# Rele-12V-FritzenLab-Testes.net
KiCad netlist of a schematic drawn in EAGLE
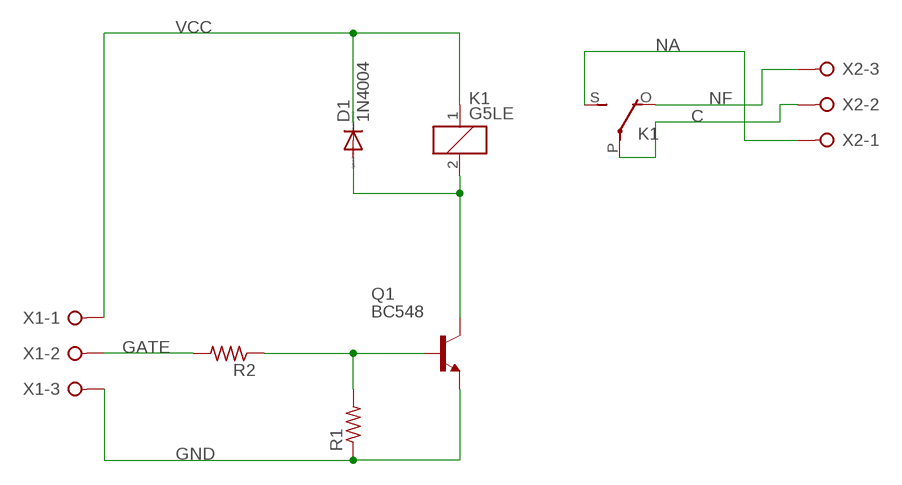
[diagram p0: schematic, sheet 1]

(export (version "E")
  (design (tool "Eeschema 10.0.6"))
  (components
    (comp (ref "D1")
      (value "1N4004")
      (footprint "eagle-import:DO41-10")
      (libsource (lib "eagle-import") (part "1N4004"))
    )
    (comp (ref "K1")
      (value "G5LE")
      (footprint "eagle-import:G5LE")
      (libsource (lib "eagle-import") (part "G5LE"))
    )
    (comp (ref "Q1")
      (value "BC548")
      (footprint "eagle-import:TO92-EBC")
      (libsource (lib "eagle-import") (part "BC548"))
    )
    (comp (ref "R1")
      (value "R-US_0207/10")
      (footprint "eagle-import:0207_10")
      (libsource (lib "eagle-import") (part "R-US_0207/10"))
    )
    (comp (ref "R2")
      (value "R-US_0207/10")
      (footprint "eagle-import:0207_10")
      (libsource (lib "eagle-import") (part "R-US_0207/10"))
    )
    (comp (ref "X1")
      (value "W237-3E")
      (footprint "eagle-import:W237-3E")
      (libsource (lib "eagle-import") (part "W237-3E"))
    )
    (comp (ref "X2")
      (value "W237-3E")
      (footprint "eagle-import:W237-3E")
      (libsource (lib "eagle-import") (part "W237-3E"))
    )
  )
  (nets
    (net (code "1") (name "/C") (class "Default")
      (node (ref "K1") (pin "P") (pinfunction "P_P") (pintype "passive"))
      (node (ref "X2") (pin "2") (pinfunction "KL_2") (pintype "passive"))
    )
    (net (code "2") (name "/GATE") (class "Default")
      (node (ref "R2") (pin "2") (pinfunction "2_2") (pintype "passive"))
      (node (ref "X1") (pin "2") (pinfunction "KL_2") (pintype "passive"))
    )
    (net (code "3") (name "/GND") (class "Default")
      (node (ref "Q1") (pin "E") (pinfunction "E_E") (pintype "passive"))
      (node (ref "R1") (pin "1") (pinfunction "1_1") (pintype "passive"))
      (node (ref "X1") (pin "3") (pinfunction "KL_3") (pintype "passive"))
    )
    (net (code "4") (name "/NA") (class "Default")
      (node (ref "K1") (pin "S") (pinfunction "S_S") (pintype "passive"))
      (node (ref "X2") (pin "1") (pinfunction "KL_1") (pintype "passive"))
    )
    (net (code "5") (name "/NF") (class "Default")
      (node (ref "K1") (pin "O") (pinfunction "O_O") (pintype "passive"))
      (node (ref "X2") (pin "3") (pinfunction "KL_3") (pintype "passive"))
    )
    (net (code "6") (name "/VCC") (class "Default")
      (node (ref "D1") (pin "C") (pinfunction "C_C") (pintype "passive"))
      (node (ref "K1") (pin "1") (pinfunction "1_1") (pintype "passive"))
      (node (ref "X1") (pin "1") (pinfunction "KL_1") (pintype "passive"))
    )
    (net (code "7") (name "Net-(D1-PadA)") (class "Default")
      (node (ref "D1") (pin "A") (pinfunction "A_A") (pintype "passive"))
      (node (ref "K1") (pin "2") (pinfunction "2_2") (pintype "passive"))
      (node (ref "Q1") (pin "C") (pinfunction "C_C") (pintype "passive"))
    )
    (net (code "8") (name "Net-(Q1-PadB)") (class "Default")
      (node (ref "Q1") (pin "B") (pinfunction "B_B") (pintype "passive"))
      (node (ref "R1") (pin "2") (pinfunction "2_2") (pintype "passive"))
      (node (ref "R2") (pin "1") (pinfunction "1_1") (pintype "passive"))
    )
  )
)
